# SAME51_PINOUT.net
KiCad netlist of a schematic drawn in Altium Designer
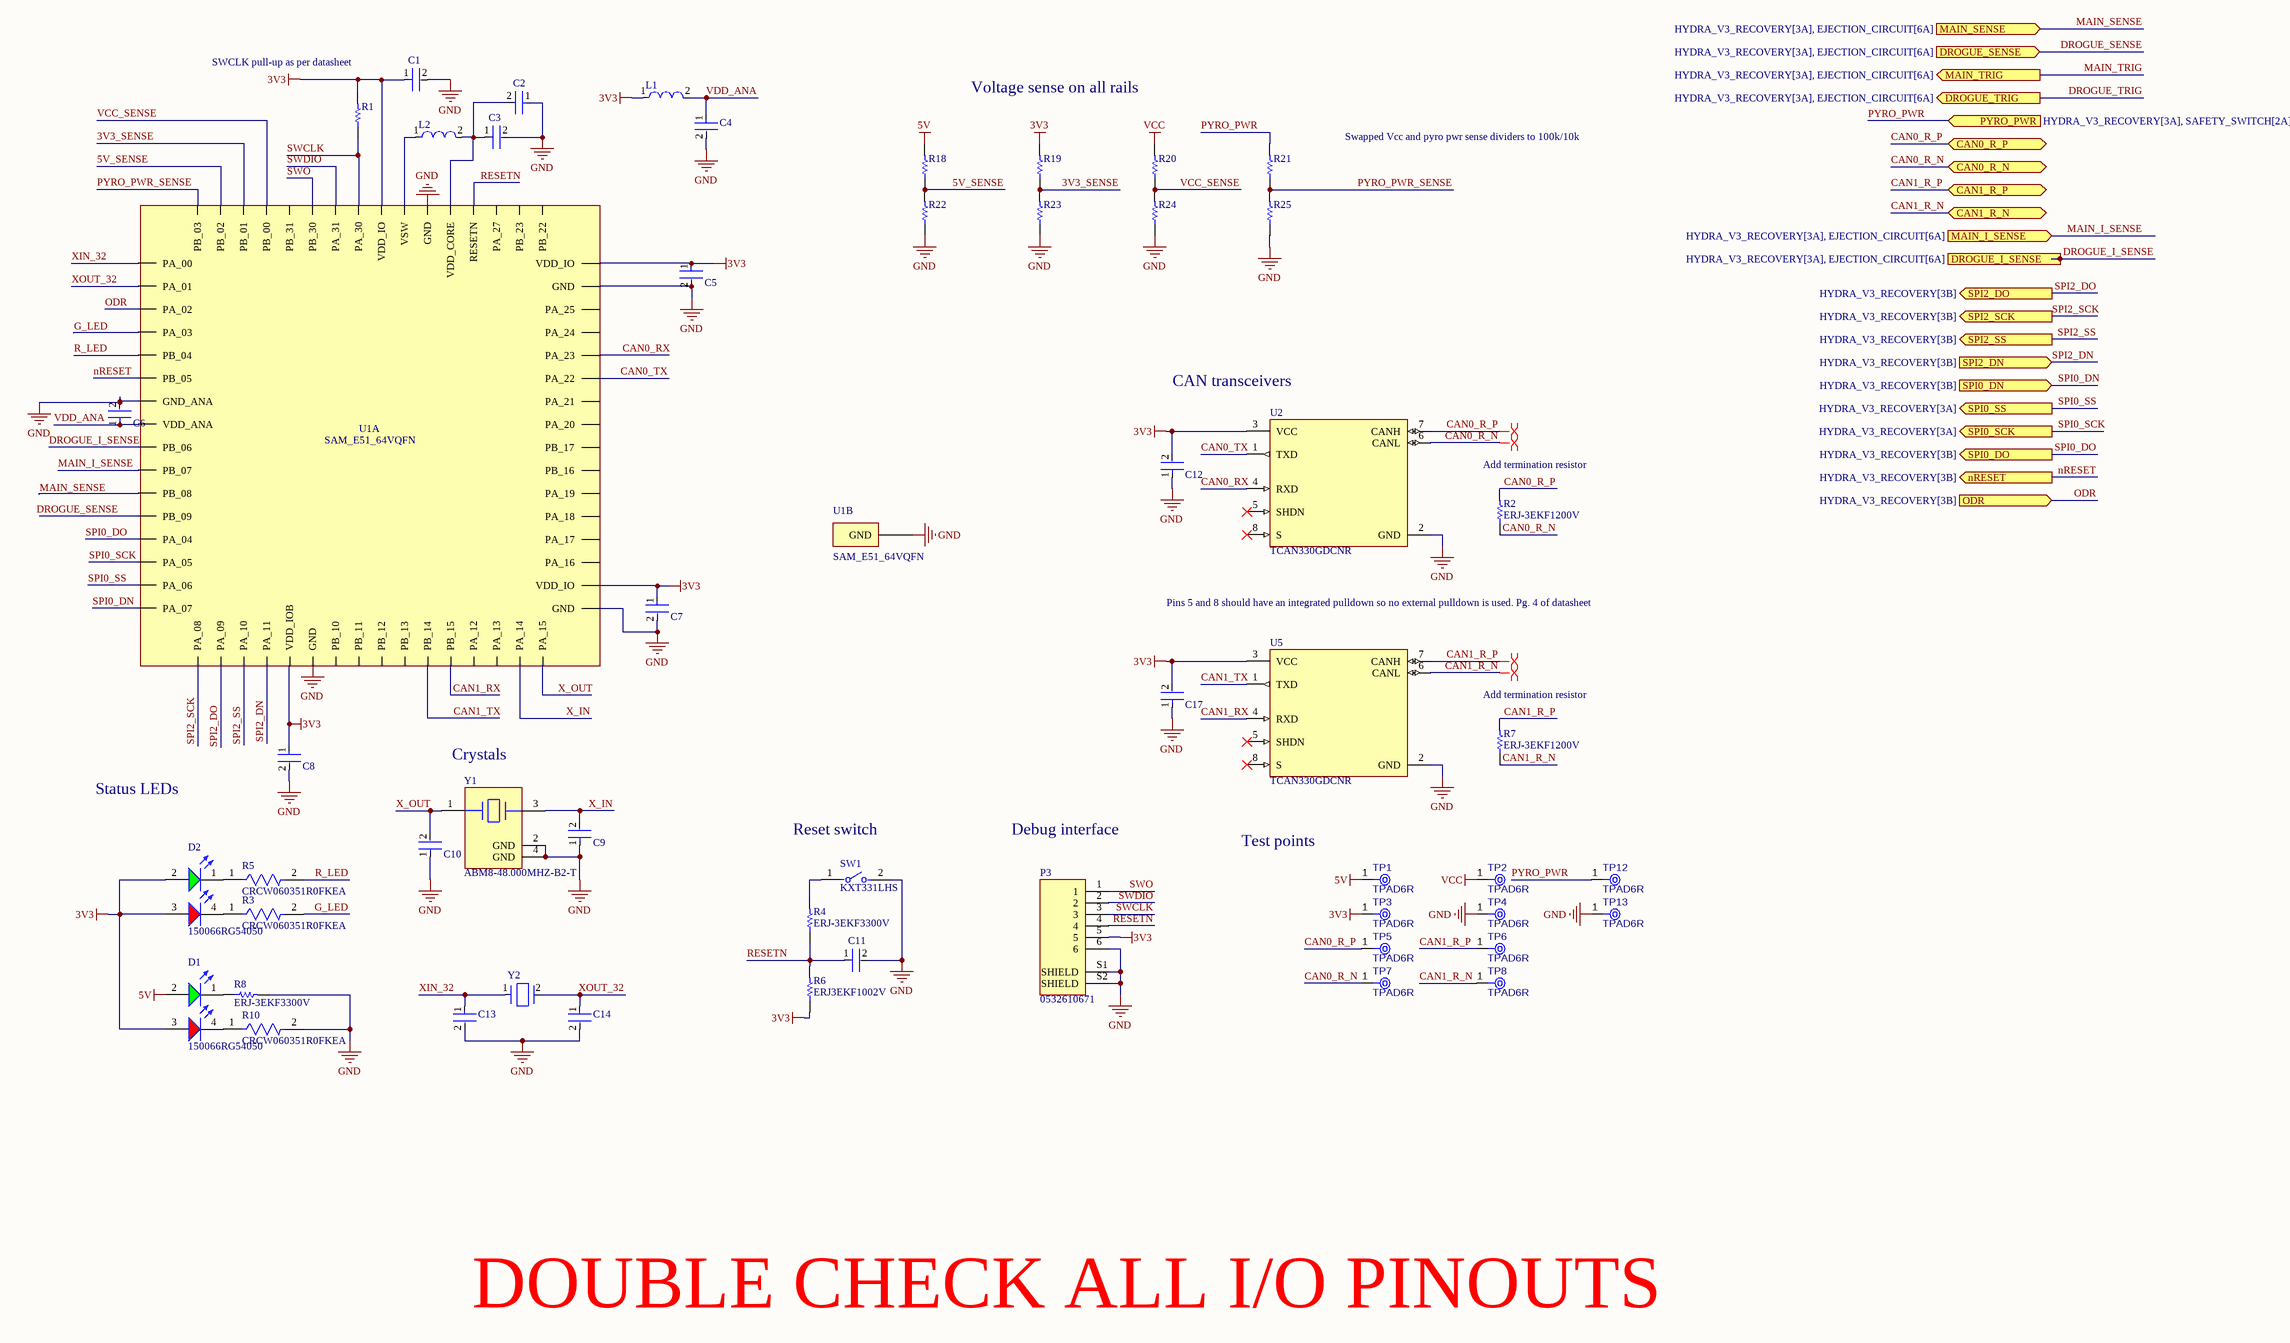
[diagram p0: SAME51_PINOUT.SchDoc]

(export (version "E")
  (design (tool "Eeschema 10.0.6"))
  (components
    (comp (ref "C1")
      (value "C0402C104K8PACTU")
      (footprint "FP-C0402-BB-MFG")
      (description "CAP CER 0.1UF 10V X5R 0402")
      (fields (field (name "MANUFACTURER") "Kemet") (field (name "TOLERANCE") "0.1"))
      (libsource (lib "Altium Content Vault") (part "b4654b650e69147ec39a6b967a45e02"))
    )
    (comp (ref "C2")
      (value "GRM155R60J475ME47D")
      (footprint "FP-GRM155-0_1-IPC_B")
      (description "Chip Multilayer Ceramic Capacitors for General Purpose, 0402, 4.7uF, X5R, 15%, 20%, 6.3V")
      (fields (field (name "VOLTAGE") "6.3V") (field (name "TOLERANCE") "20%"))
      (libsource (lib "Altium Content Vault") (part "11868f565c42a9108669ba33697ecf6"))
    )
    (comp (ref "C3")
      (value "C0402C104K8PACTU")
      (footprint "FP-C0402-BB-MFG")
      (description "CAP CER 0.1UF 10V X5R 0402")
      (fields (field (name "MANUFACTURER") "Kemet") (field (name "TOLERANCE") "0.1"))
      (libsource (lib "Altium Content Vault") (part "b4654b650e69147ec39a6b967a45e02"))
    )
    (comp (ref "C4")
      (value "C0805C106K8PACTU")
      (footprint "FP-C0805C-DG-MFG")
      (description "CAP CER 10UF 10V X5R 0805")
      (fields (field (name "TOLERANCE") "10%") (field (name "MANUFACTURER") "Kemet"))
      (libsource (lib "Altium Content Vault") (part "11868f565c42a9108669ba33697ecf6"))
    )
    (comp (ref "C5")
      (value "C0402C104K8PACTU")
      (footprint "FP-C0402-BB-MFG")
      (description "CAP CER 0.1UF 10V X5R 0402")
      (fields (field (name "MANUFACTURER") "Kemet") (field (name "TOLERANCE") "0.1"))
      (libsource (lib "Altium Content Vault") (part "b4654b650e69147ec39a6b967a45e02"))
    )
    (comp (ref "C6")
      (value "C0402C104K8PACTU")
      (footprint "FP-C0402-BB-MFG")
      (description "CAP CER 0.1UF 10V X5R 0402")
      (fields (field (name "MANUFACTURER") "Kemet") (field (name "TOLERANCE") "0.1"))
      (libsource (lib "Altium Content Vault") (part "b4654b650e69147ec39a6b967a45e02"))
    )
    (comp (ref "C7")
      (value "C0402C104K8PACTU")
      (footprint "FP-C0402-BB-MFG")
      (description "CAP CER 0.1UF 10V X5R 0402")
      (fields (field (name "MANUFACTURER") "Kemet") (field (name "TOLERANCE") "0.1"))
      (libsource (lib "Altium Content Vault") (part "b4654b650e69147ec39a6b967a45e02"))
    )
    (comp (ref "C8")
      (value "C0402C104K8PACTU")
      (footprint "FP-C0402-BB-MFG")
      (description "CAP CER 0.1UF 10V X5R 0402")
      (fields (field (name "MANUFACTURER") "Kemet") (field (name "TOLERANCE") "0.1"))
      (libsource (lib "Altium Content Vault") (part "b4654b650e69147ec39a6b967a45e02"))
    )
    (comp (ref "C9")
      (value "08051A6R8CAT2A")
      (footprint "FP-0805-L_2_01_0_2-W_1_25-MFG")
      (description "General Purpose Ceramic Capacitor, 0805, 6.8pF, 0.25pF, C0G, 30ppm/°C, 100V")
      (fields (field (name "VOLTAGE") "100V") (field (name "TOLERANCE") "5%"))
      (libsource (lib "Altium Content Vault") (part "02cd4be3c70576c341d710602a673aa"))
    )
    (comp (ref "C10")
      (value "08051A6R8CAT2A")
      (footprint "FP-0805-L_2_01_0_2-W_1_25-MFG")
      (description "General Purpose Ceramic Capacitor, 0805, 6.8pF, 0.25pF, C0G, 30ppm/°C, 100V")
      (fields (field (name "VOLTAGE") "100V") (field (name "TOLERANCE") "5%"))
      (libsource (lib "Altium Content Vault") (part "02cd4be3c70576c341d710602a673aa"))
    )
    (comp (ref "C11")
      (value "C0402C104K8PACTU")
      (footprint "FP-C0402-BB-MFG")
      (description "CAP CER 0.1UF 10V X5R 0402")
      (fields (field (name "MANUFACTURER") "Kemet") (field (name "TOLERANCE") "0.1"))
      (libsource (lib "Altium Content Vault") (part "b4654b650e69147ec39a6b967a45e02"))
    )
    (comp (ref "C12")
      (value "C0402C104K8PACTU")
      (footprint "FP-C0402-BB-MFG")
      (description "CAP CER 0.1UF 10V X5R 0402")
      (fields (field (name "MANUFACTURER") "Kemet") (field (name "TOLERANCE") "0.1"))
      (libsource (lib "Altium Content Vault") (part "b4654b650e69147ec39a6b967a45e02"))
    )
    (comp (ref "C13")
      (value "C0805C180J5GACTU")
      (footprint "FP-C0805C-DN-MFG")
      (description "CAP CER 18PF 50V C0G/NP0 0805")
      (fields
        (field (name "OCTOPART") "https://octopart.com/c0805c180j5gactu-kemet-144810")
        (field (name "TOLERANCE") "0.05")
      )
      (libsource (lib "Altium Content Vault") (part "b4654b650e69147ec39a6b967a45e02"))
    )
    (comp (ref "C14")
      (value "C0805C180J5GACTU")
      (footprint "FP-C0805C-DN-MFG")
      (description "CAP CER 18PF 50V C0G/NP0 0805")
      (fields
        (field (name "OCTOPART") "https://octopart.com/c0805c180j5gactu-kemet-144810")
        (field (name "TOLERANCE") "0.05")
      )
      (libsource (lib "Altium Content Vault") (part "b4654b650e69147ec39a6b967a45e02"))
    )
    (comp (ref "C17")
      (value "C0402C104K8PACTU")
      (footprint "FP-C0402-BB-MFG")
      (description "CAP CER 0.1UF 10V X5R 0402")
      (fields (field (name "MANUFACTURER") "Kemet") (field (name "TOLERANCE") "0.1"))
      (libsource (lib "Altium Content Vault") (part "b4654b650e69147ec39a6b967a45e02"))
    )
    (comp (ref "D1")
      (value "150066RG54050")
      (footprint "WL-SBCD_0606")
      (description "Led, Red/Grn, 180Mcd/230Mcd, 624Nm/525Nm Rohs Compliant: Yes")
      (libsource (lib "uORocketry Hardware") (part "WL-SBCD_0606_Red & Green"))
    )
    (comp (ref "D2")
      (value "150066RG54050")
      (footprint "WL-SBCD_0606")
      (description "Led, Red/Grn, 180Mcd/230Mcd, 624Nm/525Nm Rohs Compliant: Yes")
      (libsource (lib "uORocketry Hardware") (part "WL-SBCD_0606_Red & Green"))
    )
    (comp (ref "L1")
      (value "NR6028T100M")
      (footprint "FP-NR6028-MFG")
      (description "SMD Power Inductors 10uH ±20% 1.9A 84.5mΩ")
      (fields (field (name "TOLERANCE") "20%"))
      (libsource (lib "Altium Content Vault") (part "725321dda6339637d4d059423bc1c3c"))
    )
    (comp (ref "L2")
      (value "NR6028T100M")
      (footprint "FP-NR6028-MFG")
      (description "SMD Power Inductors 10uH ±20% 1.9A 84.5mΩ")
      (fields (field (name "TOLERANCE") "20%"))
      (libsource (lib "Altium Content Vault") (part "725321dda6339637d4d059423bc1c3c"))
    )
    (comp (ref "P3")
      (value "0532610671")
      (footprint "0532610671-Footprint-1")
      (description "Conn Shrouded Header (4 Sides) HDR 6 POS 1.25mm Solder RA Side Entry SMD PicoBlade™ T/R")
      (libsource (lib "uORocketry Hardware") (part "0532610671"))
    )
    (comp (ref "R1")
      (value "ERJ3EKF1002V")
      (footprint "RESC1609X55X30LL15T15")
      (description "Chip Resistor, 10 KOhm, +/- 1%, 0.1 W, -55 to 155 degC, 0603 (1608 Metric), RoHS, Tape and Reel")
      (fields (field (name "TOLERANCE") "1%") (field (name "MANUFACTURER") "Panasonic"))
      (libsource (lib "Altium Content Vault") (part "RES-2"))
    )
    (comp (ref "R2")
      (value "ERJ-3EKF1200V")
      (footprint "RESC1609X55X30ML15T15")
      (description "Chip Resistor, 120 Ohm, +/- 1%, 0.1 W, -55 to 155 degC, 0603 (1608 Metric), RoHS, Tape and Reel")
      (fields (field (name "TOLERANCE") "1%") (field (name "MANUFACTURER") "Panasonic"))
      (libsource (lib "Altium Content Vault") (part "RES-2"))
    )
    (comp (ref "R3")
      (value "CRCW060351R0FKEA")
      (footprint "FP-CRCW0603-e3-MFG")
      (description "RES Thick Film, 51Ω, 1%, 0.1W, 100ppm/°C, 0603")
      (fields (field (name "TOLERANCE") "1%"))
      (libsource (lib "Altium Content Vault") (part "1029c3af85768c4190bb7ad29bc67b5"))
    )
    (comp (ref "R4")
      (value "ERJ-3EKF3300V")
      (footprint "RESC1608X55X30LL15T15")
      (description "Chip Resistor, 330 Ohm, +/- 1%, 0.1 W, -55 to 155 degC, 0603 (1608 Metric), RoHS, Tape and Reel")
      (libsource (lib "Altium Content Vault") (part "RES-2"))
    )
    (comp (ref "R5")
      (value "CRCW060351R0FKEA")
      (footprint "FP-CRCW0603-e3-MFG")
      (description "RES Thick Film, 51Ω, 1%, 0.1W, 100ppm/°C, 0603")
      (fields (field (name "TOLERANCE") "1%"))
      (libsource (lib "Altium Content Vault") (part "1029c3af85768c4190bb7ad29bc67b5"))
    )
    (comp (ref "R6")
      (value "ERJ3EKF1002V")
      (footprint "RESC1609X55X30LL15T15")
      (description "Chip Resistor, 10 KOhm, +/- 1%, 0.1 W, -55 to 155 degC, 0603 (1608 Metric), RoHS, Tape and Reel")
      (fields (field (name "TOLERANCE") "1%") (field (name "MANUFACTURER") "Panasonic"))
      (libsource (lib "Altium Content Vault") (part "RES-2"))
    )
    (comp (ref "R7")
      (value "ERJ-3EKF1200V")
      (footprint "RESC1609X55X30ML15T15")
      (description "Chip Resistor, 120 Ohm, +/- 1%, 0.1 W, -55 to 155 degC, 0603 (1608 Metric), RoHS, Tape and Reel")
      (fields (field (name "TOLERANCE") "1%") (field (name "MANUFACTURER") "Panasonic"))
      (libsource (lib "Altium Content Vault") (part "RES-2"))
    )
    (comp (ref "R8")
      (value "ERJ-3EKF3300V")
      (footprint "RESC1608X55X30LL15T15")
      (description "Chip Resistor, 330 Ohm, +/- 1%, 0.1 W, -55 to 155 degC, 0603 (1608 Metric), RoHS, Tape and Reel")
      (libsource (lib "Altium Content Vault") (part "RES-2"))
    )
    (comp (ref "R10")
      (value "CRCW060351R0FKEA")
      (footprint "FP-CRCW0603-e3-MFG")
      (description "RES Thick Film, 51Ω, 1%, 0.1W, 100ppm/°C, 0603")
      (fields (field (name "TOLERANCE") "1%"))
      (libsource (lib "Altium Content Vault") (part "1029c3af85768c4190bb7ad29bc67b5"))
    )
    (comp (ref "R18")
      (value "ERJ3EKF1002V")
      (footprint "RESC1609X55X30LL15T15")
      (description "Chip Resistor, 10 KOhm, +/- 1%, 0.1 W, -55 to 155 degC, 0603 (1608 Metric), RoHS, Tape and Reel")
      (fields (field (name "TOLERANCE") "1%") (field (name "MANUFACTURER") "Panasonic"))
      (libsource (lib "Altium Content Vault") (part "RES-2"))
    )
    (comp (ref "R19")
      (value "ERJ3EKF1002V")
      (footprint "RESC1609X55X30LL15T15")
      (description "Chip Resistor, 10 KOhm, +/- 1%, 0.1 W, -55 to 155 degC, 0603 (1608 Metric), RoHS, Tape and Reel")
      (fields (field (name "TOLERANCE") "1%") (field (name "MANUFACTURER") "Panasonic"))
      (libsource (lib "Altium Content Vault") (part "RES-2"))
    )
    (comp (ref "R20")
      (value "ERJ-3EKF1003V")
      (footprint "RESC1608X55X30ML15T15")
      (fields (field (name "MANUFACTURER") "Panasonic"))
      (libsource (lib "Altium Content Vault") (part "RES"))
    )
    (comp (ref "R21")
      (value "ERJ-3EKF1003V")
      (footprint "RESC1608X55X30ML15T15")
      (fields (field (name "MANUFACTURER") "Panasonic"))
      (libsource (lib "Altium Content Vault") (part "RES"))
    )
    (comp (ref "R22")
      (value "ERJ3EKF1002V")
      (footprint "RESC1609X55X30LL15T15")
      (description "Chip Resistor, 10 KOhm, +/- 1%, 0.1 W, -55 to 155 degC, 0603 (1608 Metric), RoHS, Tape and Reel")
      (fields (field (name "TOLERANCE") "1%") (field (name "MANUFACTURER") "Panasonic"))
      (libsource (lib "Altium Content Vault") (part "RES-2"))
    )
    (comp (ref "R23")
      (value "ERJ3EKF1002V")
      (footprint "RESC1609X55X30LL15T15")
      (description "Chip Resistor, 10 KOhm, +/- 1%, 0.1 W, -55 to 155 degC, 0603 (1608 Metric), RoHS, Tape and Reel")
      (fields (field (name "TOLERANCE") "1%") (field (name "MANUFACTURER") "Panasonic"))
      (libsource (lib "Altium Content Vault") (part "RES-2"))
    )
    (comp (ref "R24")
      (value "ERJ3EKF1002V")
      (footprint "RESC1609X55X30LL15T15")
      (description "Chip Resistor, 10 KOhm, +/- 1%, 0.1 W, -55 to 155 degC, 0603 (1608 Metric), RoHS, Tape and Reel")
      (fields (field (name "TOLERANCE") "1%") (field (name "MANUFACTURER") "Panasonic"))
      (libsource (lib "Altium Content Vault") (part "RES-2"))
    )
    (comp (ref "R25")
      (value "ERJ3EKF1002V")
      (footprint "RESC1609X55X30LL15T15")
      (description "Chip Resistor, 10 KOhm, +/- 1%, 0.1 W, -55 to 155 degC, 0603 (1608 Metric), RoHS, Tape and Reel")
      (fields (field (name "TOLERANCE") "1%") (field (name "MANUFACTURER") "Panasonic"))
      (libsource (lib "Altium Content Vault") (part "RES-2"))
    )
    (comp (ref "SW1")
      (value "KXT331LHS")
      (footprint "FP-KXT331LHS-MFG")
      (description "SWITCH TACTILE SPST-NO 0.02A 15V")
      (libsource (lib "Altium Content Vault") (part "bb27bde45df87f1f469753f287ef5ae"))
    )
    (comp (ref "TP1")
      (value "TPAD6R")
      (footprint "TP06R")
      (description "0.6mm round")
      (libsource (lib "uORocketry Hardware") (part "CMP-001-0001-4"))
    )
    (comp (ref "TP2")
      (value "TPAD6R")
      (footprint "TP06R")
      (description "0.6mm round")
      (libsource (lib "uORocketry Hardware") (part "CMP-001-0001-4"))
    )
    (comp (ref "TP3")
      (value "TPAD6R")
      (footprint "TP06R")
      (description "0.6mm round")
      (libsource (lib "uORocketry Hardware") (part "CMP-001-0001-4"))
    )
    (comp (ref "TP4")
      (value "TPAD6R")
      (footprint "TP06R")
      (description "0.6mm round")
      (libsource (lib "uORocketry Hardware") (part "CMP-001-0001-4"))
    )
    (comp (ref "TP5")
      (value "TPAD6R")
      (footprint "TP06R")
      (description "0.6mm round")
      (libsource (lib "uORocketry Hardware") (part "CMP-001-0001-4"))
    )
    (comp (ref "TP6")
      (value "TPAD6R")
      (footprint "TP06R")
      (description "0.6mm round")
      (libsource (lib "uORocketry Hardware") (part "CMP-001-0001-4"))
    )
    (comp (ref "TP7")
      (value "TPAD6R")
      (footprint "TP06R")
      (description "0.6mm round")
      (libsource (lib "uORocketry Hardware") (part "CMP-001-0001-4"))
    )
    (comp (ref "TP8")
      (value "TPAD6R")
      (footprint "TP06R")
      (description "0.6mm round")
      (libsource (lib "uORocketry Hardware") (part "CMP-001-0001-4"))
    )
    (comp (ref "TP12")
      (value "TPAD6R")
      (footprint "TP06R")
      (description "0.6mm round")
      (libsource (lib "uORocketry Hardware") (part "CMP-001-0001-4"))
    )
    (comp (ref "TP13")
      (value "TPAD6R")
      (footprint "TP06R")
      (description "0.6mm round")
      (libsource (lib "uORocketry Hardware") (part "CMP-001-0001-4"))
    )
    (comp (ref "U1")
      (value "SAM_E51_64VQFN")
      (footprint "SAM_E51_64VQFN-Footprint-1")
      (description "Rudimentary symbol and footprint for the SAM E51 microcontroller")
      (libsource (lib "uORocketry Hardware") (part "SAM_E51_64VQFN-Symbol-1"))
    )
    (comp (ref "U2")
      (value "TCAN330GDCNR")
      (footprint "FP-DCN0008A-MFG")
      (description "IC TRANSCEIVER 1/1 SOT23-8")
      (libsource (lib "Altium Content Vault") (part "22681b49c22ad38c6a4e12e04c36c7a"))
    )
    (comp (ref "U5")
      (value "TCAN330GDCNR")
      (footprint "FP-DCN0008A-MFG")
      (description "IC TRANSCEIVER 1/1 SOT23-8")
      (libsource (lib "Altium Content Vault") (part "22681b49c22ad38c6a4e12e04c36c7a"))
    )
    (comp (ref "Y1")
      (value "ABM8-48.000MHZ-B2-T")
      (footprint "FP-ABM8-MFG")
      (description "Crystal 48MHz ±20ppm 18pF SMD-4 3.2mm x 2.5mm")
      (fields (field (name "TOLERANCE") "20ppm"))
      (libsource (lib "Altium Content Vault") (part "dfdb7f9a12507849fb681da9a70121c"))
    )
    (comp (ref "Y2")
      (value "ECS-.327-12.5-1210-TR")
      (footprint "FP-ECX-1210-MFG")
      (description "CRYSTAL 32.7680KHZ 12.5PF SMD")
      (fields
        (field (name "OCTOPART") "https://octopart.com/ecs-.327-12.5-1210-tr-ecs+international-81221340")
        (field (name "TOLERANCE") "20ppm")
      )
      (libsource (lib "Altium Content Vault") (part "99724985039315a44fd0d1401b84e49"))
    )
  )
  (nets
    (net (code "1") (name "/3V3_SENSE") (class "Default")
      (node (ref "R19") (pin "1") (pinfunction "1_1") (pintype "passive"))
      (node (ref "R23") (pin "2") (pinfunction "2_2") (pintype "passive"))
      (node (ref "U1") (pin "62") (pinfunction "PB_01_62") (pintype "passive"))
    )
    (net (code "2") (name "/5V_SENSE") (class "Default")
      (node (ref "R18") (pin "1") (pinfunction "1_1") (pintype "passive"))
      (node (ref "R22") (pin "2") (pinfunction "2_2") (pintype "passive"))
      (node (ref "U1") (pin "63") (pinfunction "PB_02_63") (pintype "passive"))
    )
    (net (code "3") (name "/CAN0_RX") (class "Default")
      (node (ref "U1") (pin "44") (pinfunction "PA_23_44") (pintype "passive"))
      (node (ref "U2") (pin "4") (pinfunction "RXD_4") (pintype "input"))
    )
    (net (code "4") (name "/CAN0_R_N") (class "Default")
      (node (ref "R2") (pin "1") (pinfunction "1_1") (pintype "passive"))
      (node (ref "TP7") (pin "1") (pinfunction "TP_1") (pintype "passive"))
      (node (ref "U2") (pin "6") (pinfunction "CANL_6") (pintype "bidirectional"))
    )
    (net (code "5") (name "/CAN0_R_P") (class "Default")
      (node (ref "R2") (pin "2") (pinfunction "2_2") (pintype "passive"))
      (node (ref "TP5") (pin "1") (pinfunction "TP_1") (pintype "passive"))
      (node (ref "U2") (pin "7") (pinfunction "CANH_7") (pintype "bidirectional"))
    )
    (net (code "6") (name "/CAN0_TX") (class "Default")
      (node (ref "U1") (pin "43") (pinfunction "PA_22_43") (pintype "passive"))
      (node (ref "U2") (pin "1") (pinfunction "TXD_1") (pintype "output"))
    )
    (net (code "7") (name "/CAN1_RX") (class "Default")
      (node (ref "U1") (pin "28") (pinfunction "PB_15_28") (pintype "passive"))
      (node (ref "U5") (pin "4") (pinfunction "RXD_4") (pintype "input"))
    )
    (net (code "8") (name "/CAN1_R_N") (class "Default")
      (node (ref "R7") (pin "1") (pinfunction "1_1") (pintype "passive"))
      (node (ref "TP8") (pin "1") (pinfunction "TP_1") (pintype "passive"))
      (node (ref "U5") (pin "6") (pinfunction "CANL_6") (pintype "bidirectional"))
    )
    (net (code "9") (name "/CAN1_R_P") (class "Default")
      (node (ref "R7") (pin "2") (pinfunction "2_2") (pintype "passive"))
      (node (ref "TP6") (pin "1") (pinfunction "TP_1") (pintype "passive"))
      (node (ref "U5") (pin "7") (pinfunction "CANH_7") (pintype "bidirectional"))
    )
    (net (code "10") (name "/CAN1_TX") (class "Default")
      (node (ref "U1") (pin "27") (pinfunction "PB_14_27") (pintype "passive"))
      (node (ref "U5") (pin "1") (pinfunction "TXD_1") (pintype "output"))
    )
    (net (code "11") (name "/DROGUE_I_SENSE") (class "Default")
      (node (ref "U1") (pin "9") (pinfunction "PB_06_9") (pintype "passive"))
    )
    (net (code "12") (name "/DROGUE_SENSE") (class "Default")
      (node (ref "U1") (pin "12") (pinfunction "PB_09_12") (pintype "passive"))
    )
    (net (code "14") (name "/G_LED") (class "Default")
      (node (ref "R3") (pin "2") (pinfunction "2_2") (pintype "passive"))
      (node (ref "U1") (pin "4") (pinfunction "PA_03_4") (pintype "passive"))
    )
    (net (code "15") (name "/MAIN_I_SENSE") (class "Default")
      (node (ref "U1") (pin "10") (pinfunction "PB_07_10") (pintype "passive"))
    )
    (net (code "16") (name "/MAIN_SENSE") (class "Default")
      (node (ref "U1") (pin "11") (pinfunction "PB_08_11") (pintype "passive"))
    )
    (net (code "18") (name "/ODR") (class "Default")
      (node (ref "U1") (pin "3") (pinfunction "PA_02_3") (pintype "passive"))
    )
    (net (code "19") (name "/PYRO_PWR") (class "Default")
      (node (ref "R21") (pin "2") (pinfunction "2_2") (pintype "passive"))
      (node (ref "TP12") (pin "1") (pinfunction "TP_1") (pintype "passive"))
    )
    (net (code "20") (name "/PYRO_PWR_SENSE") (class "Default")
      (node (ref "R21") (pin "1") (pinfunction "1_1") (pintype "passive"))
      (node (ref "R25") (pin "2") (pinfunction "2_2") (pintype "passive"))
      (node (ref "U1") (pin "64") (pinfunction "PB_03_64") (pintype "passive"))
    )
    (net (code "21") (name "/RESETN") (class "Default")
      (node (ref "C11") (pin "1") (pinfunction "1_1") (pintype "passive"))
      (node (ref "P3") (pin "4") (pinfunction "4_4") (pintype "passive"))
      (node (ref "R4") (pin "1") (pinfunction "1_1") (pintype "passive"))
      (node (ref "R6") (pin "2") (pinfunction "2_2") (pintype "passive"))
      (node (ref "U1") (pin "52") (pinfunction "RESETN_52") (pintype "passive"))
    )
    (net (code "22") (name "/R_LED") (class "Default")
      (node (ref "R5") (pin "2") (pinfunction "2_2") (pintype "passive"))
      (node (ref "U1") (pin "5") (pinfunction "PB_04_5") (pintype "passive"))
    )
    (net (code "23") (name "/SPI0_DN") (class "Default")
      (node (ref "U1") (pin "16") (pinfunction "PA_07_16") (pintype "passive"))
    )
    (net (code "24") (name "/SPI0_DO") (class "Default")
      (node (ref "U1") (pin "13") (pinfunction "PA_04_13") (pintype "passive"))
    )
    (net (code "25") (name "/SPI0_SCK") (class "Default")
      (node (ref "U1") (pin "14") (pinfunction "PA_05_14") (pintype "passive"))
    )
    (net (code "26") (name "/SPI0_SS") (class "Default")
      (node (ref "U1") (pin "15") (pinfunction "PA_06_15") (pintype "passive"))
    )
    (net (code "27") (name "/SPI2_DN") (class "Default")
      (node (ref "U1") (pin "20") (pinfunction "PA_11_20") (pintype "passive"))
    )
    (net (code "28") (name "/SPI2_DO") (class "Default")
      (node (ref "U1") (pin "18") (pinfunction "PA_09_18") (pintype "passive"))
    )
    (net (code "29") (name "/SPI2_SCK") (class "Default")
      (node (ref "U1") (pin "17") (pinfunction "PA_08_17") (pintype "passive"))
    )
    (net (code "30") (name "/SPI2_SS") (class "Default")
      (node (ref "U1") (pin "19") (pinfunction "PA_10_19") (pintype "passive"))
    )
    (net (code "31") (name "/SWCLK") (class "Default")
      (node (ref "P3") (pin "3") (pinfunction "3_3") (pintype "passive"))
      (node (ref "R1") (pin "1") (pinfunction "1_1") (pintype "passive"))
      (node (ref "U1") (pin "57") (pinfunction "PA_30_57") (pintype "passive"))
    )
    (net (code "32") (name "/SWDIO") (class "Default")
      (node (ref "P3") (pin "2") (pinfunction "2_2") (pintype "passive"))
      (node (ref "U1") (pin "58") (pinfunction "PA_31_58") (pintype "passive"))
    )
    (net (code "33") (name "/SWO") (class "Default")
      (node (ref "P3") (pin "1") (pinfunction "1_1") (pintype "passive"))
      (node (ref "U1") (pin "59") (pinfunction "PB_30_59") (pintype "passive"))
    )
    (net (code "34") (name "/VCC_SENSE") (class "Default")
      (node (ref "R20") (pin "1") (pinfunction "1_1") (pintype "passive"))
      (node (ref "R24") (pin "2") (pinfunction "2_2") (pintype "passive"))
      (node (ref "U1") (pin "61") (pinfunction "PB_00_61") (pintype "passive"))
    )
    (net (code "35") (name "/VDD_ANA") (class "Default")
      (node (ref "C4") (pin "1") (pinfunction "1_1") (pintype "passive"))
      (node (ref "C6") (pin "1") (pinfunction "1_1") (pintype "passive"))
      (node (ref "L1") (pin "2") (pinfunction "2_2") (pintype "passive"))
      (node (ref "U1") (pin "8") (pinfunction "VDD_ANA_8") (pintype "passive"))
    )
    (net (code "36") (name "/XIN_32") (class "Default")
      (node (ref "C13") (pin "1") (pinfunction "1_1") (pintype "passive"))
      (node (ref "U1") (pin "1") (pinfunction "PA_00_1") (pintype "passive"))
      (node (ref "Y2") (pin "1") (pinfunction "In/Out_1") (pintype "passive"))
    )
    (net (code "37") (name "/XOUT_32") (class "Default")
      (node (ref "C14") (pin "1") (pinfunction "1_1") (pintype "passive"))
      (node (ref "U1") (pin "2") (pinfunction "PA_01_2") (pintype "passive"))
      (node (ref "Y2") (pin "2") (pinfunction "Out/In_2") (pintype "passive"))
    )
    (net (code "38") (name "/X_IN") (class "Default")
      (node (ref "C9") (pin "2") (pinfunction "2_2") (pintype "passive"))
      (node (ref "U1") (pin "31") (pinfunction "PA_14_31") (pintype "passive"))
      (node (ref "Y1") (pin "3") (pinfunction "3_3") (pintype "passive"))
    )
    (net (code "39") (name "/X_OUT") (class "Default")
      (node (ref "C10") (pin "2") (pinfunction "2_2") (pintype "passive"))
      (node (ref "U1") (pin "32") (pinfunction "PA_15_32") (pintype "passive"))
      (node (ref "Y1") (pin "1") (pinfunction "1_1") (pintype "passive"))
    )
    (net (code "40") (name "/nRESET") (class "Default")
      (node (ref "U1") (pin "6") (pinfunction "PB_05_6") (pintype "passive"))
    )
    (net (code "41") (name "3V3") (class "Default")
      (node (ref "C1") (pin "1") (pinfunction "1_1") (pintype "passive"))
      (node (ref "C12") (pin "2") (pinfunction "2_2") (pintype "passive"))
      (node (ref "C17") (pin "2") (pinfunction "2_2") (pintype "passive"))
      (node (ref "C5") (pin "1") (pinfunction "1_1") (pintype "passive"))
      (node (ref "C7") (pin "1") (pinfunction "1_1") (pintype "passive"))
      (node (ref "C8") (pin "1") (pinfunction "1_1") (pintype "passive"))
      (node (ref "D1") (pin "3") (pinfunction "A_3") (pintype "passive"))
      (node (ref "D2") (pin "2") (pinfunction "A_2") (pintype "passive"))
      (node (ref "D2") (pin "3") (pinfunction "A_3") (pintype "passive"))
      (node (ref "L1") (pin "1") (pinfunction "1_1") (pintype "passive"))
      (node (ref "P3") (pin "5") (pinfunction "5_5") (pintype "passive"))
      (node (ref "R1") (pin "2") (pinfunction "2_2") (pintype "passive"))
      (node (ref "R19") (pin "2") (pinfunction "2_2") (pintype "passive"))
      (node (ref "R6") (pin "1") (pinfunction "1_1") (pintype "passive"))
      (node (ref "TP3") (pin "1") (pinfunction "TP_1") (pintype "passive"))
      (node (ref "U1") (pin "21") (pinfunction "VDD_IOB_21") (pintype "passive"))
      (node (ref "U1") (pin "34") (pinfunction "VDD_IO_34") (pintype "passive"))
      (node (ref "U1") (pin "48") (pinfunction "VDD_IO_48") (pintype "passive"))
      (node (ref "U1") (pin "56") (pinfunction "VDD_IO_56") (pintype "passive"))
      (node (ref "U2") (pin "3") (pinfunction "VCC_3") (pintype "power_in"))
      (node (ref "U5") (pin "3") (pinfunction "VCC_3") (pintype "power_in"))
    )
    (net (code "42") (name "5V") (class "Default")
      (node (ref "D1") (pin "2") (pinfunction "A_2") (pintype "passive"))
      (node (ref "R18") (pin "2") (pinfunction "2_2") (pintype "passive"))
      (node (ref "TP1") (pin "1") (pinfunction "TP_1") (pintype "passive"))
    )
    (net (code "43") (name "GND") (class "Default")
      (node (ref "C1") (pin "2") (pinfunction "2_2") (pintype "passive"))
      (node (ref "C10") (pin "1") (pinfunction "1_1") (pintype "passive"))
      (node (ref "C11") (pin "2") (pinfunction "2_2") (pintype "passive"))
      (node (ref "C12") (pin "1") (pinfunction "1_1") (pintype "passive"))
      (node (ref "C13") (pin "2") (pinfunction "2_2") (pintype "passive"))
      (node (ref "C14") (pin "2") (pinfunction "2_2") (pintype "passive"))
      (node (ref "C17") (pin "1") (pinfunction "1_1") (pintype "passive"))
      (node (ref "C2") (pin "1") (pinfunction "1_1") (pintype "passive"))
      (node (ref "C3") (pin "2") (pinfunction "2_2") (pintype "passive"))
      (node (ref "C4") (pin "2") (pinfunction "2_2") (pintype "passive"))
      (node (ref "C5") (pin "2") (pinfunction "2_2") (pintype "passive"))
      (node (ref "C6") (pin "2") (pinfunction "2_2") (pintype "passive"))
      (node (ref "C7") (pin "2") (pinfunction "2_2") (pintype "passive"))
      (node (ref "C8") (pin "2") (pinfunction "2_2") (pintype "passive"))
      (node (ref "C9") (pin "1") (pinfunction "1_1") (pintype "passive"))
      (node (ref "P3") (pin "6") (pinfunction "6_6") (pintype "passive"))
      (node (ref "P3") (pin "S1") (pinfunction "SHIELD_S1") (pintype "passive"))
      (node (ref "P3") (pin "S2") (pinfunction "SHIELD_S2") (pintype "passive"))
      (node (ref "R10") (pin "2") (pinfunction "2_2") (pintype "passive"))
      (node (ref "R22") (pin "1") (pinfunction "1_1") (pintype "passive"))
      (node (ref "R23") (pin "1") (pinfunction "1_1") (pintype "passive"))
      (node (ref "R24") (pin "1") (pinfunction "1_1") (pintype "passive"))
      (node (ref "R25") (pin "1") (pinfunction "1_1") (pintype "passive"))
      (node (ref "R8") (pin "2") (pinfunction "2_2") (pintype "passive"))
      (node (ref "SW1") (pin "2") (pinfunction "2_2") (pintype "passive"))
      (node (ref "TP13") (pin "1") (pinfunction "TP_1") (pintype "passive"))
      (node (ref "TP4") (pin "1") (pinfunction "TP_1") (pintype "passive"))
      (node (ref "U1") (pin "22") (pinfunction "GND_22") (pintype "passive"))
      (node (ref "U1") (pin "33") (pinfunction "GND_33") (pintype "passive"))
      (node (ref "U1") (pin "47") (pinfunction "GND_47") (pintype "passive"))
      (node (ref "U1") (pin "54") (pinfunction "GND_54") (pintype "passive"))
      (node (ref "U1") (pin "65") (pinfunction "GND_65") (pintype "passive"))
      (node (ref "U1") (pin "7") (pinfunction "GND_ANA_7") (pintype "passive"))
      (node (ref "U2") (pin "2") (pinfunction "GND_2") (pintype "power_in"))
      (node (ref "U5") (pin "2") (pinfunction "GND_2") (pintype "power_in"))
      (node (ref "Y1") (pin "2") (pinfunction "GND_2") (pintype "power_in"))
      (node (ref "Y1") (pin "4") (pinfunction "GND_4") (pintype "power_in"))
    )
    (net (code "44") (name "Net-(D1-K-Pad1)") (class "Default")
      (node (ref "D1") (pin "1") (pinfunction "K_1") (pintype "passive"))
      (node (ref "R8") (pin "1") (pinfunction "1_1") (pintype "passive"))
    )
    (net (code "45") (name "Net-(D1-K-Pad4)") (class "Default")
      (node (ref "D1") (pin "4") (pinfunction "K_4") (pintype "passive"))
      (node (ref "R10") (pin "1") (pinfunction "1_1") (pintype "passive"))
    )
    (net (code "46") (name "Net-(D2-K-Pad1)") (class "Default")
      (node (ref "D2") (pin "1") (pinfunction "K_1") (pintype "passive"))
      (node (ref "R5") (pin "1") (pinfunction "1_1") (pintype "passive"))
    )
    (net (code "47") (name "Net-(D2-K-Pad4)") (class "Default")
      (node (ref "D2") (pin "4") (pinfunction "K_4") (pintype "passive"))
      (node (ref "R3") (pin "1") (pinfunction "1_1") (pintype "passive"))
    )
    (net (code "48") (name "Net-(R4-Pad2)") (class "Default")
      (node (ref "R4") (pin "2") (pinfunction "2_2") (pintype "passive"))
      (node (ref "SW1") (pin "1") (pinfunction "1_1") (pintype "passive"))
    )
    (net (code "49") (name "Net-(U1A-VDD_CORE)") (class "Default")
      (node (ref "C2") (pin "2") (pinfunction "2_2") (pintype "passive"))
      (node (ref "C3") (pin "1") (pinfunction "1_1") (pintype "passive"))
      (node (ref "L2") (pin "2") (pinfunction "2_2") (pintype "passive"))
      (node (ref "U1") (pin "53") (pinfunction "VDD_CORE_53") (pintype "passive"))
    )
    (net (code "50") (name "Net-(U1A-VSW)") (class "Default")
      (node (ref "L2") (pin "1") (pinfunction "1_1") (pintype "passive"))
      (node (ref "U1") (pin "55") (pinfunction "VSW_55") (pintype "passive"))
    )
    (net (code "51") (name "VCC") (class "Default")
      (node (ref "R20") (pin "2") (pinfunction "2_2") (pintype "passive"))
      (node (ref "TP2") (pin "1") (pinfunction "TP_1") (pintype "passive"))
    )
    (net (code "52") (name "unconnected-(U1A-PA_12-Pad29)") (class "Default")
      (node (ref "U1") (pin "29") (pinfunction "PA_12_29") (pintype "passive"))
    )
    (net (code "53") (name "unconnected-(U1A-PA_13-Pad30)") (class "Default")
      (node (ref "U1") (pin "30") (pinfunction "PA_13_30") (pintype "passive"))
    )
    (net (code "54") (name "unconnected-(U1A-PA_16-Pad35)") (class "Default")
      (node (ref "U1") (pin "35") (pinfunction "PA_16_35") (pintype "passive"))
    )
    (net (code "55") (name "unconnected-(U1A-PA_17-Pad36)") (class "Default")
      (node (ref "U1") (pin "36") (pinfunction "PA_17_36") (pintype "passive"))
    )
    (net (code "56") (name "unconnected-(U1A-PA_18-Pad37)") (class "Default")
      (node (ref "U1") (pin "37") (pinfunction "PA_18_37") (pintype "passive"))
    )
    (net (code "57") (name "unconnected-(U1A-PA_19-Pad38)") (class "Default")
      (node (ref "U1") (pin "38") (pinfunction "PA_19_38") (pintype "passive"))
    )
    (net (code "58") (name "unconnected-(U1A-PA_20-Pad41)") (class "Default")
      (node (ref "U1") (pin "41") (pinfunction "PA_20_41") (pintype "passive"))
    )
    (net (code "59") (name "unconnected-(U1A-PA_21-Pad42)") (class "Default")
      (node (ref "U1") (pin "42") (pinfunction "PA_21_42") (pintype "passive"))
    )
    (net (code "60") (name "unconnected-(U1A-PA_24-Pad45)") (class "Default")
      (node (ref "U1") (pin "45") (pinfunction "PA_24_45") (pintype "passive"))
    )
    (net (code "61") (name "unconnected-(U1A-PA_25-Pad46)") (class "Default")
      (node (ref "U1") (pin "46") (pinfunction "PA_25_46") (pintype "passive"))
    )
    (net (code "62") (name "unconnected-(U1A-PA_27-Pad51)") (class "Default")
      (node (ref "U1") (pin "51") (pinfunction "PA_27_51") (pintype "passive"))
    )
    (net (code "63") (name "unconnected-(U1A-PB_10-Pad23)") (class "Default")
      (node (ref "U1") (pin "23") (pinfunction "PB_10_23") (pintype "passive"))
    )
    (net (code "64") (name "unconnected-(U1A-PB_11-Pad24)") (class "Default")
      (node (ref "U1") (pin "24") (pinfunction "PB_11_24") (pintype "passive"))
    )
    (net (code "65") (name "unconnected-(U1A-PB_12-Pad25)") (class "Default")
      (node (ref "U1") (pin "25") (pinfunction "PB_12_25") (pintype "passive"))
    )
    (net (code "66") (name "unconnected-(U1A-PB_13-Pad26)") (class "Default")
      (node (ref "U1") (pin "26") (pinfunction "PB_13_26") (pintype "passive"))
    )
    (net (code "67") (name "unconnected-(U1A-PB_16-Pad39)") (class "Default")
      (node (ref "U1") (pin "39") (pinfunction "PB_16_39") (pintype "passive"))
    )
    (net (code "68") (name "unconnected-(U1A-PB_17-Pad40)") (class "Default")
      (node (ref "U1") (pin "40") (pinfunction "PB_17_40") (pintype "passive"))
    )
    (net (code "69") (name "unconnected-(U1A-PB_22-Pad49)") (class "Default")
      (node (ref "U1") (pin "49") (pinfunction "PB_22_49") (pintype "passive"))
    )
    (net (code "70") (name "unconnected-(U1A-PB_23-Pad50)") (class "Default")
      (node (ref "U1") (pin "50") (pinfunction "PB_23_50") (pintype "passive"))
    )
    (net (code "71") (name "unconnected-(U1A-PB_31-Pad60)") (class "Default")
      (node (ref "U1") (pin "60") (pinfunction "PB_31_60") (pintype "passive"))
    )
    (net (code "72") (name "unconnected-(U2-S-Pad8)") (class "Default")
      (node (ref "U2") (pin "8") (pinfunction "S_8") (pintype "input+no_connect"))
    )
    (net (code "73") (name "unconnected-(U2-SHDN-Pad5)") (class "Default")
      (node (ref "U2") (pin "5") (pinfunction "SHDN_5") (pintype "input+no_connect"))
    )
    (net (code "74") (name "unconnected-(U5-S-Pad8)") (class "Default")
      (node (ref "U5") (pin "8") (pinfunction "S_8") (pintype "input+no_connect"))
    )
    (net (code "75") (name "unconnected-(U5-SHDN-Pad5)") (class "Default")
      (node (ref "U5") (pin "5") (pinfunction "SHDN_5") (pintype "input+no_connect"))
    )
  )
)
